# motorcontroller_updated_3.net
KiCad netlist of a schematic drawn in Altium Designer
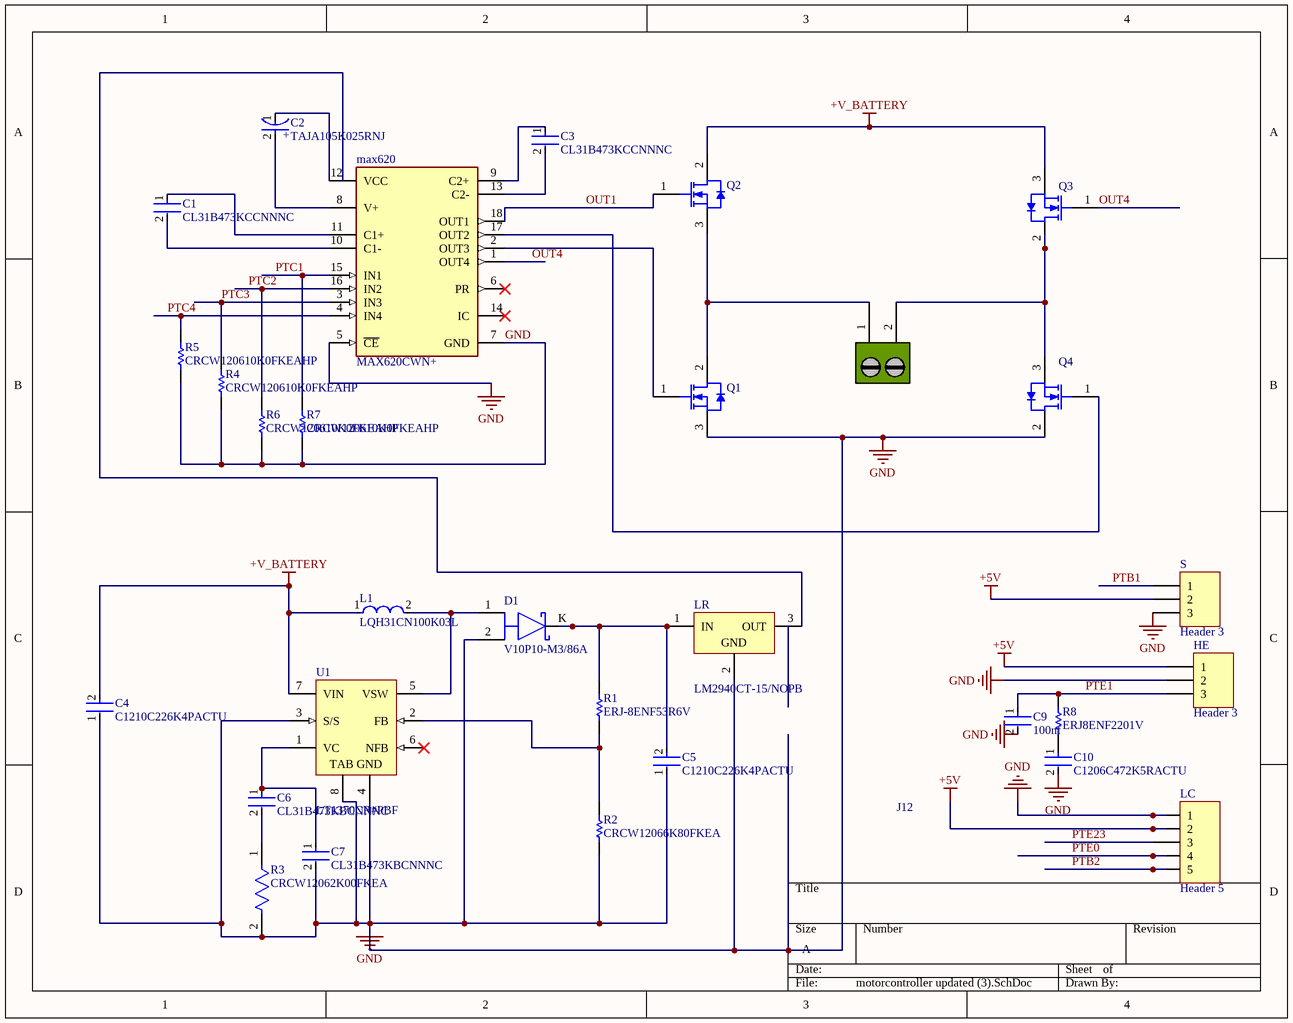
[diagram p0: motorcontroller updated (3).SchDoc]

(export (version "E")
  (design (tool "Eeschema 10.0.6"))
  (components
    (comp (ref "C1")
      (value "CL31B473KCCNNNC")
      (footprint "FP-CL31-IPC_B")
      (description "Cap Ceramic 47nF 100V X7R ±10% SMD 1206 +125°C Embossed T/R")
      (fields (field (name "TOLERANCE") "10%") (field (name "VOLTAGE") "63V"))
      (libsource (lib "Altium Content Vault") (part "b4654b650e69147ec39a6b967a45e02"))
    )
    (comp (ref "C2")
      (value "TAJA105K025RNJ")
      (footprint "FP-TAJA-MFG")
      (description "1uF 25V  ±10% 8Ω 1206  SMD Tantalum Capacitor")
      (fields (field (name "TOLERANCE") "20%") (field (name "VOLTAGE") "25V"))
      (libsource (lib "Altium Content Vault") (part "203bc49f2ac43e59fd269a8c329ed05"))
    )
    (comp (ref "C3")
      (value "CL31B473KCCNNNC")
      (footprint "FP-CL31-IPC_B")
      (description "Cap Ceramic 47nF 100V X7R ±10% SMD 1206 +125°C Embossed T/R")
      (fields (field (name "TOLERANCE") "10%") (field (name "VOLTAGE") "63V"))
      (libsource (lib "Altium Content Vault") (part "b4654b650e69147ec39a6b967a45e02"))
    )
    (comp (ref "C4")
      (value "C1210C226K4PACTU")
      (footprint "FP-C1210C226K4PACTU-MFG")
      (description "CAP CER 22UF 16V X5R 1210")
      (fields (field (name "VOLTAGE") "16V") (field (name "TOLERANCE") "10%"))
      (libsource (lib "Altium Content Vault") (part "236180d848d6139a670b325ea6854c9"))
    )
    (comp (ref "C5")
      (value "C1210C226K4PACTU")
      (footprint "FP-C1210C226K4PACTU-MFG")
      (description "CAP CER 22UF 16V X5R 1210")
      (fields (field (name "VOLTAGE") "16V") (field (name "TOLERANCE") "10%"))
      (libsource (lib "Altium Content Vault") (part "236180d848d6139a670b325ea6854c9"))
    )
    (comp (ref "C6")
      (value "CL31B473KBCNNNC")
      (footprint "FP-CL31-IPC_B")
      (description "Cap Ceramic 47nF 50V X7R ±10% SMD 1206 +125°C Embossed T/R")
      (fields (field (name "TOLERANCE") "10%") (field (name "VOLTAGE") "50V"))
      (libsource (lib "Altium Content Vault") (part "b4654b650e69147ec39a6b967a45e02"))
    )
    (comp (ref "C7")
      (value "CL31B473KBCNNNC")
      (footprint "FP-CL31-IPC_B")
      (description "Cap Ceramic 47nF 50V X7R ±10% SMD 1206 +125°C Embossed T/R")
      (fields (field (name "TOLERANCE") "10%") (field (name "VOLTAGE") "50V"))
      (libsource (lib "Altium Content Vault") (part "b4654b650e69147ec39a6b967a45e02"))
    )
    (comp (ref "C9")
      (value "100nf")
      (footprint "FP-CL31-IPC_C")
      (description "Cap Ceramic 100nF 100V X7R ±10% SMD 1206 +125°C Embossed T/R")
      (fields (field (name "VOLTAGE") "100V") (field (name "TOLERANCE") "10%"))
      (libsource (lib "Altium Content Vault") (part "b4654b650e69147ec39a6b967a45e02"))
    )
    (comp (ref "C10")
      (value "C1206C472K5RACTU")
      (footprint "FP-C1206C-EB-MFG")
      (description "CAP CER 4700PF 50V X7R 1206")
      (fields (field (name "TOLERANCE") "0.1") (field (name "MANUFACTURER") "KEMET"))
      (libsource (lib "Altium Content Vault") (part "b4654b650e69147ec39a6b967a45e02"))
    )
    (comp (ref "D1")
      (value "V10P10-M3/86A")
      (footprint "FP-95570-MFG")
      (description "DIODE SCHOTTKY 100V 10A TO277A")
      (fields
        (field (name "OCTOPART") "https://octopart.com/v10p10-m3%2F86a-vishay-42522004")
        (field (name "MANUFACTURER") "Vishay")
      )
      (libsource (lib "Altium Content Vault") (part "875e16d92aa1343137ed61b5eab5252"))
    )
    (comp (ref "HE")
      (value "Header 3")
      (footprint "HDR1X3")
      (description "Header, 3-Pin")
      (fields (field (name "PUBLISHER") "Altium Limited"))
      (libsource (lib "Miscellaneous Connectors") (part "Header 3"))
    )
    (comp (ref "J12")
      (value "~")
      (footprint "282857-2")
      (description "Buchanan, Terminal Block Connector, 2 Position, 5.08 mm, 24A, 300 VAC, 30 to 12 AWG")
      (fields
        (field (name "MANUFACTURER") "TE Connectivity")
        (field (name "MANUFACTURER PART NUMBER") "282857-2")
      )
      (libsource (lib "eConnector") (part "282857-2"))
    )
    (comp (ref "L1")
      (value "LQH31CN100K03L")
      (footprint "FP-LQH31CN_03-MFG")
      (description "Wire Wound Ferrite Inductor for Power Lines 10μH ±10% 1.69Ω 230mA 1206")
      (fields (field (name "TOLERANCE") "10%"))
      (libsource (lib "Altium Content Vault") (part "725321dda6339637d4d059423bc1c3c"))
    )
    (comp (ref "LC")
      (value "Header 5")
      (footprint "HDR1X5")
      (description "Header, 5-Pin")
      (fields (field (name "PUBLISHER") "Altium Limited"))
      (libsource (lib "Miscellaneous Connectors") (part "Header 5"))
    )
    (comp (ref "LR")
      (value "LM2940CT-15/NOPB")
      (footprint "NDE0003A")
      (description "1A Low Dropout Regulator, 3-pin TO-220, Pb-Free")
      (fields (field (name "MANUFACTURER") "Texas Instruments"))
      (libsource (lib "Altium Content Vault") (part "PM-REG-LM2940-SIL3"))
    )
    (comp (ref "max620")
      (value "MAX620CWN+")
      (footprint "FP-W18-1-MFG")
      (description "IC GATE DRVR HIGH-SIDE 18SOIC")
      (libsource (lib "Altium Content Vault") (part "c2ec74dac6dc176bf3e825ca6eb1ba2"))
    )
    (comp (ref "Q1")
      (value "~")
      (footprint "INF-PG-TO252-3-11_A_M")
      (fields
        (field (name "MANUFACTURER") "Infineon")
        (field (name "PARTNUMBER") "IPD060N03L G")
        (field (name "MANUFACTURER PART NUMBER") "IPD060N03LG")
      )
      (libsource (lib "Altium Content Vault") (part "INF-NEMOS-GDS-3"))
    )
    (comp (ref "Q2")
      (value "~")
      (footprint "INF-PG-TO252-3-11_A_M")
      (fields
        (field (name "MANUFACTURER") "Infineon")
        (field (name "PARTNUMBER") "IPD060N03L G")
        (field (name "MANUFACTURER PART NUMBER") "IPD060N03LG")
      )
      (libsource (lib "Altium Content Vault") (part "INF-NEMOS-GDS-3"))
    )
    (comp (ref "Q3")
      (value "~")
      (footprint "INF-PG-TO252-3-11_A_M")
      (fields
        (field (name "MANUFACTURER") "Infineon")
        (field (name "PARTNUMBER") "IPD060N03L G")
        (field (name "MANUFACTURER PART NUMBER") "IPD060N03LG")
      )
      (libsource (lib "Altium Content Vault") (part "INF-NEMOS-GDS-3"))
    )
    (comp (ref "Q4")
      (value "~")
      (footprint "INF-PG-TO252-3-11_A_M")
      (fields
        (field (name "MANUFACTURER") "Infineon")
        (field (name "PARTNUMBER") "IPD060N03L G")
        (field (name "MANUFACTURER PART NUMBER") "IPD060N03LG")
      )
      (libsource (lib "Altium Content Vault") (part "INF-NEMOS-GDS-3"))
    )
    (comp (ref "R1")
      (value "ERJ-8ENF53R6V")
      (footprint "RESC3216X70X50NL05T20")
      (fields (field (name "MANUFACTURER") "Panasonic"))
      (libsource (lib "Altium Content Vault") (part "RES"))
    )
    (comp (ref "R2")
      (value "CRCW12066K80FKEA")
      (footprint "RESC3216X60X45LL10T20")
      (fields (field (name "MANUFACTURER") "Vishay Dale"))
      (libsource (lib "Altium Content Vault") (part "RES"))
    )
    (comp (ref "R3")
      (value "CRCW12062K00FKEA")
      (footprint "FP-CRCW1206-e3-IPC_A")
      (description "RES Thick Film, 2kΩ, 1%, 0.25W, 100ppm/°C, 1206")
      (fields (field (name "TOLERANCE") "1%") (field (name "MANUFACTURER") "Vishay"))
      (libsource (lib "Altium Content Vault") (part "1029c3af85768c4190bb7ad29bc67b5"))
    )
    (comp (ref "R4")
      (value "CRCW120610K0FKEAHP")
      (footprint "RESC3116X65X50NL20T20")
      (fields (field (name "MANUFACTURER") "Vishay Dale"))
      (libsource (lib "Altium Content Vault") (part "RES"))
    )
    (comp (ref "R5")
      (value "CRCW120610K0FKEAHP")
      (footprint "RESC3116X65X50NL20T20")
      (fields (field (name "MANUFACTURER") "Vishay Dale"))
      (libsource (lib "Altium Content Vault") (part "RES"))
    )
    (comp (ref "R6")
      (value "CRCW120610K0FKEAHP")
      (footprint "RESC3116X65X50NL20T20")
      (fields (field (name "MANUFACTURER") "Vishay Dale"))
      (libsource (lib "Altium Content Vault") (part "RES"))
    )
    (comp (ref "R7")
      (value "CRCW120610K0FKEAHP")
      (footprint "RESC3116X65X50NL20T20")
      (fields (field (name "MANUFACTURER") "Vishay Dale"))
      (libsource (lib "Altium Content Vault") (part "RES"))
    )
    (comp (ref "R8")
      (value "ERJ8ENF2201V")
      (footprint "RESC3216X70X50NL05T20")
      (fields (field (name "MANUFACTURER") "Panasonic"))
      (libsource (lib "Altium Content Vault") (part "RES"))
    )
    (comp (ref "S")
      (value "Header 3")
      (footprint "HDR1X3")
      (description "Header, 3-Pin")
      (fields (field (name "PUBLISHER") "Altium Limited"))
      (libsource (lib "Miscellaneous Connectors") (part "Header 3"))
    )
    (comp (ref "U1")
      (value "LT1370CR#PBF")
      (footprint "LT-R-7_L")
      (description "500 kHz High Efficiency 6 A Switching Regulator, 7-pin DPAK (R-7), 0 to 125 degC, Pb-Free")
      (fields (field (name "MANUFACTURER") "Linear Technology"))
      (libsource (lib "Altium Content Vault") (part "LT-LT1370X-R-7"))
    )
  )
  (nets
    (net (code "1") (name "+5V") (class "Default")
      (node (ref "HE") (pin "1") (pinfunction "1_1") (pintype "passive"))
      (node (ref "LC") (pin "2") (pinfunction "2_2") (pintype "passive"))
      (node (ref "S") (pin "2") (pinfunction "2_2") (pintype "passive"))
    )
    (net (code "2") (name "+V_BATTERY") (class "Default")
      (node (ref "C4") (pin "2") (pinfunction "2_2") (pintype "passive"))
      (node (ref "L1") (pin "1") (pinfunction "1_1") (pintype "passive"))
      (node (ref "Q2") (pin "2") (pinfunction "DRAIN_2") (pintype "passive"))
      (node (ref "Q3") (pin "3") (pinfunction "SOURCE_3") (pintype "passive"))
      (node (ref "U1") (pin "7") (pinfunction "VIN_7") (pintype "power_in"))
    )
    (net (code "3") (name "/OUT1") (class "Default")
      (node (ref "Q2") (pin "1") (pinfunction "GATE_1") (pintype "passive"))
      (node (ref "max620") (pin "18") (pinfunction "OUT1_18") (pintype "output"))
    )
    (net (code "4") (name "/OUT4") (class "Default")
      (node (ref "Q3") (pin "1") (pinfunction "GATE_1") (pintype "passive"))
      (node (ref "max620") (pin "1") (pinfunction "OUT4_1") (pintype "output"))
    )
    (net (code "5") (name "/PTB1") (class "Default")
      (node (ref "S") (pin "1") (pinfunction "1_1") (pintype "passive"))
    )
    (net (code "6") (name "/PTB2") (class "Default")
      (node (ref "LC") (pin "5") (pinfunction "5_5") (pintype "passive"))
    )
    (net (code "7") (name "/PTC1") (class "Default")
      (node (ref "R7") (pin "1") (pinfunction "1_1") (pintype "passive"))
      (node (ref "max620") (pin "15") (pinfunction "IN1_15") (pintype "input"))
    )
    (net (code "8") (name "/PTC2") (class "Default")
      (node (ref "R6") (pin "2") (pinfunction "2_2") (pintype "passive"))
      (node (ref "max620") (pin "16") (pinfunction "IN2_16") (pintype "input"))
    )
    (net (code "9") (name "/PTC3") (class "Default")
      (node (ref "R4") (pin "1") (pinfunction "1_1") (pintype "passive"))
      (node (ref "max620") (pin "3") (pinfunction "IN3_3") (pintype "input"))
    )
    (net (code "10") (name "/PTC4") (class "Default")
      (node (ref "R5") (pin "2") (pinfunction "2_2") (pintype "passive"))
      (node (ref "max620") (pin "4") (pinfunction "IN4_4") (pintype "input"))
    )
    (net (code "11") (name "/PTE0") (class "Default")
      (node (ref "LC") (pin "4") (pinfunction "4_4") (pintype "passive"))
    )
    (net (code "12") (name "/PTE1") (class "Default")
      (node (ref "C9") (pin "1") (pinfunction "1_1") (pintype "passive"))
      (node (ref "HE") (pin "3") (pinfunction "3_3") (pintype "passive"))
      (node (ref "R8") (pin "2") (pinfunction "2_2") (pintype "passive"))
    )
    (net (code "13") (name "/PTE23") (class "Default")
      (node (ref "LC") (pin "3") (pinfunction "3_3") (pintype "passive"))
    )
    (net (code "14") (name "GND") (class "Default")
      (node (ref "C10") (pin "2") (pinfunction "2_2") (pintype "passive"))
      (node (ref "C4") (pin "1") (pinfunction "1_1") (pintype "passive"))
      (node (ref "C5") (pin "1") (pinfunction "1_1") (pintype "passive"))
      (node (ref "C7") (pin "2") (pinfunction "2_2") (pintype "passive"))
      (node (ref "C9") (pin "2") (pinfunction "2_2") (pintype "passive"))
      (node (ref "D1") (pin "2") (pinfunction "A_2") (pintype "passive"))
      (node (ref "HE") (pin "2") (pinfunction "2_2") (pintype "passive"))
      (node (ref "LC") (pin "1") (pinfunction "1_1") (pintype "passive"))
      (node (ref "LR") (pin "2") (pinfunction "GND_2") (pintype "power_in"))
      (node (ref "Q1") (pin "3") (pinfunction "SOURCE_3") (pintype "passive"))
      (node (ref "Q4") (pin "2") (pinfunction "DRAIN_2") (pintype "passive"))
      (node (ref "R2") (pin "2") (pinfunction "2_2") (pintype "passive"))
      (node (ref "R3") (pin "2") (pinfunction "2_2") (pintype "passive"))
      (node (ref "R4") (pin "2") (pinfunction "2_2") (pintype "passive"))
      (node (ref "R5") (pin "1") (pinfunction "1_1") (pintype "passive"))
      (node (ref "R6") (pin "1") (pinfunction "1_1") (pintype "passive"))
      (node (ref "R7") (pin "2") (pinfunction "2_2") (pintype "passive"))
      (node (ref "S") (pin "3") (pinfunction "3_3") (pintype "passive"))
      (node (ref "U1") (pin "3") (pinfunction "S/S_3") (pintype "input"))
      (node (ref "U1") (pin "4") (pinfunction "GND_4") (pintype "power_in"))
      (node (ref "U1") (pin "8") (pinfunction "TAB_8") (pintype "power_in"))
      (node (ref "max620") (pin "5") (pinfunction "~{CE}_5") (pintype "input"))
      (node (ref "max620") (pin "7") (pinfunction "GND_7") (pintype "power_in"))
    )
    (net (code "15") (name "Net-(C2-A)") (class "Default")
      (node (ref "C2") (pin "2") (pinfunction "A_2") (pintype "passive"))
      (node (ref "max620") (pin "8") (pinfunction "V+_8") (pintype "power_in"))
    )
    (net (code "16") (name "Net-(C2-C)") (class "Default")
      (node (ref "C2") (pin "1") (pinfunction "C_1") (pintype "passive"))
      (node (ref "max620") (pin "12") (pinfunction "VCC_12") (pintype "power_in"))
    )
    (net (code "17") (name "Net-(C6-Pad2)") (class "Default")
      (node (ref "C6") (pin "2") (pinfunction "2_2") (pintype "passive"))
      (node (ref "R3") (pin "1") (pinfunction "1_1") (pintype "passive"))
    )
    (net (code "18") (name "Net-(C10-Pad1)") (class "Default")
      (node (ref "C10") (pin "1") (pinfunction "1_1") (pintype "passive"))
      (node (ref "R8") (pin "1") (pinfunction "1_1") (pintype "passive"))
    )
    (net (code "19") (name "Net-(D1-C)") (class "Default")
      (node (ref "C5") (pin "2") (pinfunction "2_2") (pintype "passive"))
      (node (ref "D1") (pin "K") (pinfunction "C_K") (pintype "passive"))
      (node (ref "LR") (pin "1") (pinfunction "IN_1") (pintype "power_in"))
      (node (ref "R1") (pin "2") (pinfunction "2_2") (pintype "passive"))
    )
    (net (code "20") (name "Net-(Q1-DRAIN)") (class "Default")
      (node (ref "J12") (pin "1") (pinfunction "1_1") (pintype "passive"))
      (node (ref "Q1") (pin "2") (pinfunction "DRAIN_2") (pintype "passive"))
      (node (ref "Q2") (pin "3") (pinfunction "SOURCE_3") (pintype "passive"))
    )
    (net (code "21") (name "Net-(Q1-GATE)") (class "Default")
      (node (ref "Q1") (pin "1") (pinfunction "GATE_1") (pintype "passive"))
      (node (ref "max620") (pin "2") (pinfunction "OUT3_2") (pintype "output"))
    )
    (net (code "22") (name "Net-(Q3-DRAIN)") (class "Default")
      (node (ref "J12") (pin "2") (pinfunction "2_2") (pintype "passive"))
      (node (ref "Q3") (pin "2") (pinfunction "DRAIN_2") (pintype "passive"))
      (node (ref "Q4") (pin "3") (pinfunction "SOURCE_3") (pintype "passive"))
    )
    (net (code "23") (name "Net-(Q4-GATE)") (class "Default")
      (node (ref "Q4") (pin "1") (pinfunction "GATE_1") (pintype "passive"))
      (node (ref "max620") (pin "17") (pinfunction "OUT2_17") (pintype "output"))
    )
    (net (code "24") (name "Net-(U1-FB)") (class "Default")
      (node (ref "R1") (pin "1") (pinfunction "1_1") (pintype "passive"))
      (node (ref "R2") (pin "1") (pinfunction "1_1") (pintype "passive"))
      (node (ref "U1") (pin "2") (pinfunction "FB_2") (pintype "input"))
    )
    (net (code "25") (name "Net-(U1-VC)") (class "Default")
      (node (ref "C6") (pin "1") (pinfunction "1_1") (pintype "passive"))
      (node (ref "C7") (pin "1") (pinfunction "1_1") (pintype "passive"))
      (node (ref "U1") (pin "1") (pinfunction "VC_1") (pintype "passive"))
    )
    (net (code "26") (name "Net-(U1-VSW)") (class "Default")
      (node (ref "D1") (pin "1") (pinfunction "A_1") (pintype "passive"))
      (node (ref "L1") (pin "2") (pinfunction "2_2") (pintype "passive"))
      (node (ref "U1") (pin "5") (pinfunction "VSW_5") (pintype "power_in"))
    )
    (net (code "27") (name "Net-(max620-C1+)") (class "Default")
      (node (ref "C1") (pin "1") (pinfunction "1_1") (pintype "passive"))
      (node (ref "max620") (pin "11") (pinfunction "C1+_11") (pintype "passive"))
    )
    (net (code "28") (name "Net-(max620-C1-)") (class "Default")
      (node (ref "C1") (pin "2") (pinfunction "2_2") (pintype "passive"))
      (node (ref "max620") (pin "10") (pinfunction "C1-_10") (pintype "passive"))
    )
    (net (code "29") (name "Net-(max620-C2+)") (class "Default")
      (node (ref "C3") (pin "1") (pinfunction "1_1") (pintype "passive"))
      (node (ref "max620") (pin "9") (pinfunction "C2+_9") (pintype "passive"))
    )
    (net (code "30") (name "Net-(max620-C2-)") (class "Default")
      (node (ref "C3") (pin "2") (pinfunction "2_2") (pintype "passive"))
      (node (ref "max620") (pin "13") (pinfunction "C2-_13") (pintype "passive"))
    )
    (net (code "31") (name "unconnected-(LR-OUT-Pad3)") (class "Default")
      (node (ref "LR") (pin "3") (pinfunction "OUT_3") (pintype "power_in"))
    )
    (net (code "32") (name "unconnected-(U1-NFB-Pad6)") (class "Default")
      (node (ref "U1") (pin "6") (pinfunction "NFB_6") (pintype "input+no_connect"))
    )
    (net (code "33") (name "unconnected-(max620-IC-Pad14)") (class "Default")
      (node (ref "max620") (pin "14") (pinfunction "IC_14") (pintype "passive+no_connect"))
    )
    (net (code "34") (name "unconnected-(max620-PR-Pad6)") (class "Default")
      (node (ref "max620") (pin "6") (pinfunction "PR_6") (pintype "output+no_connect"))
    )
  )
)
